# AZPR_EvBoard.net
KiCad netlist of a schematic drawn in EAGLE
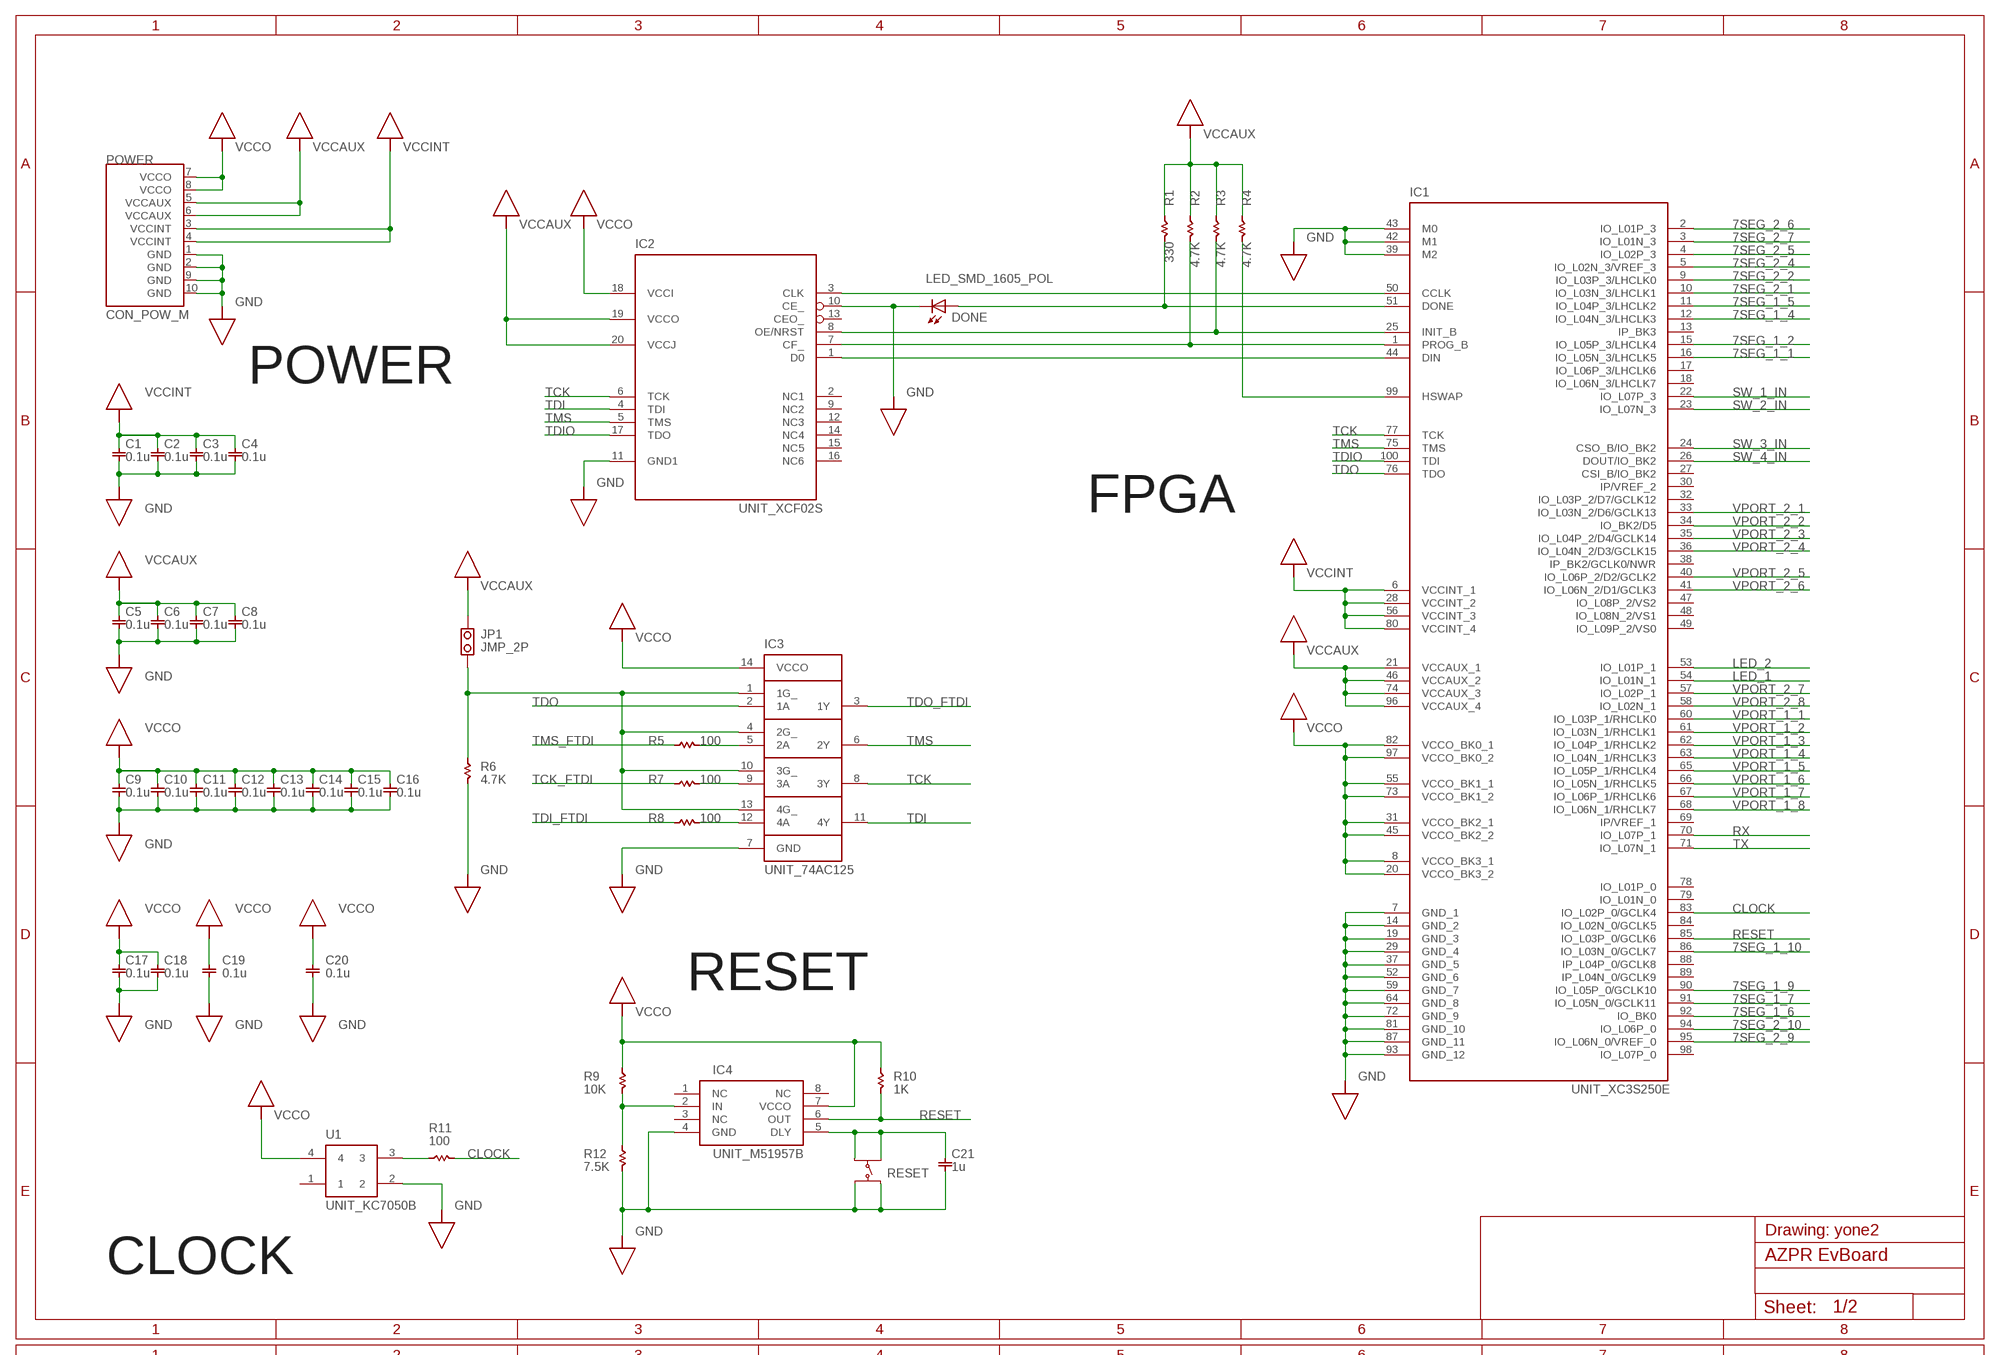
[diagram p0: schematic, sheet 1, part 1 of 2]
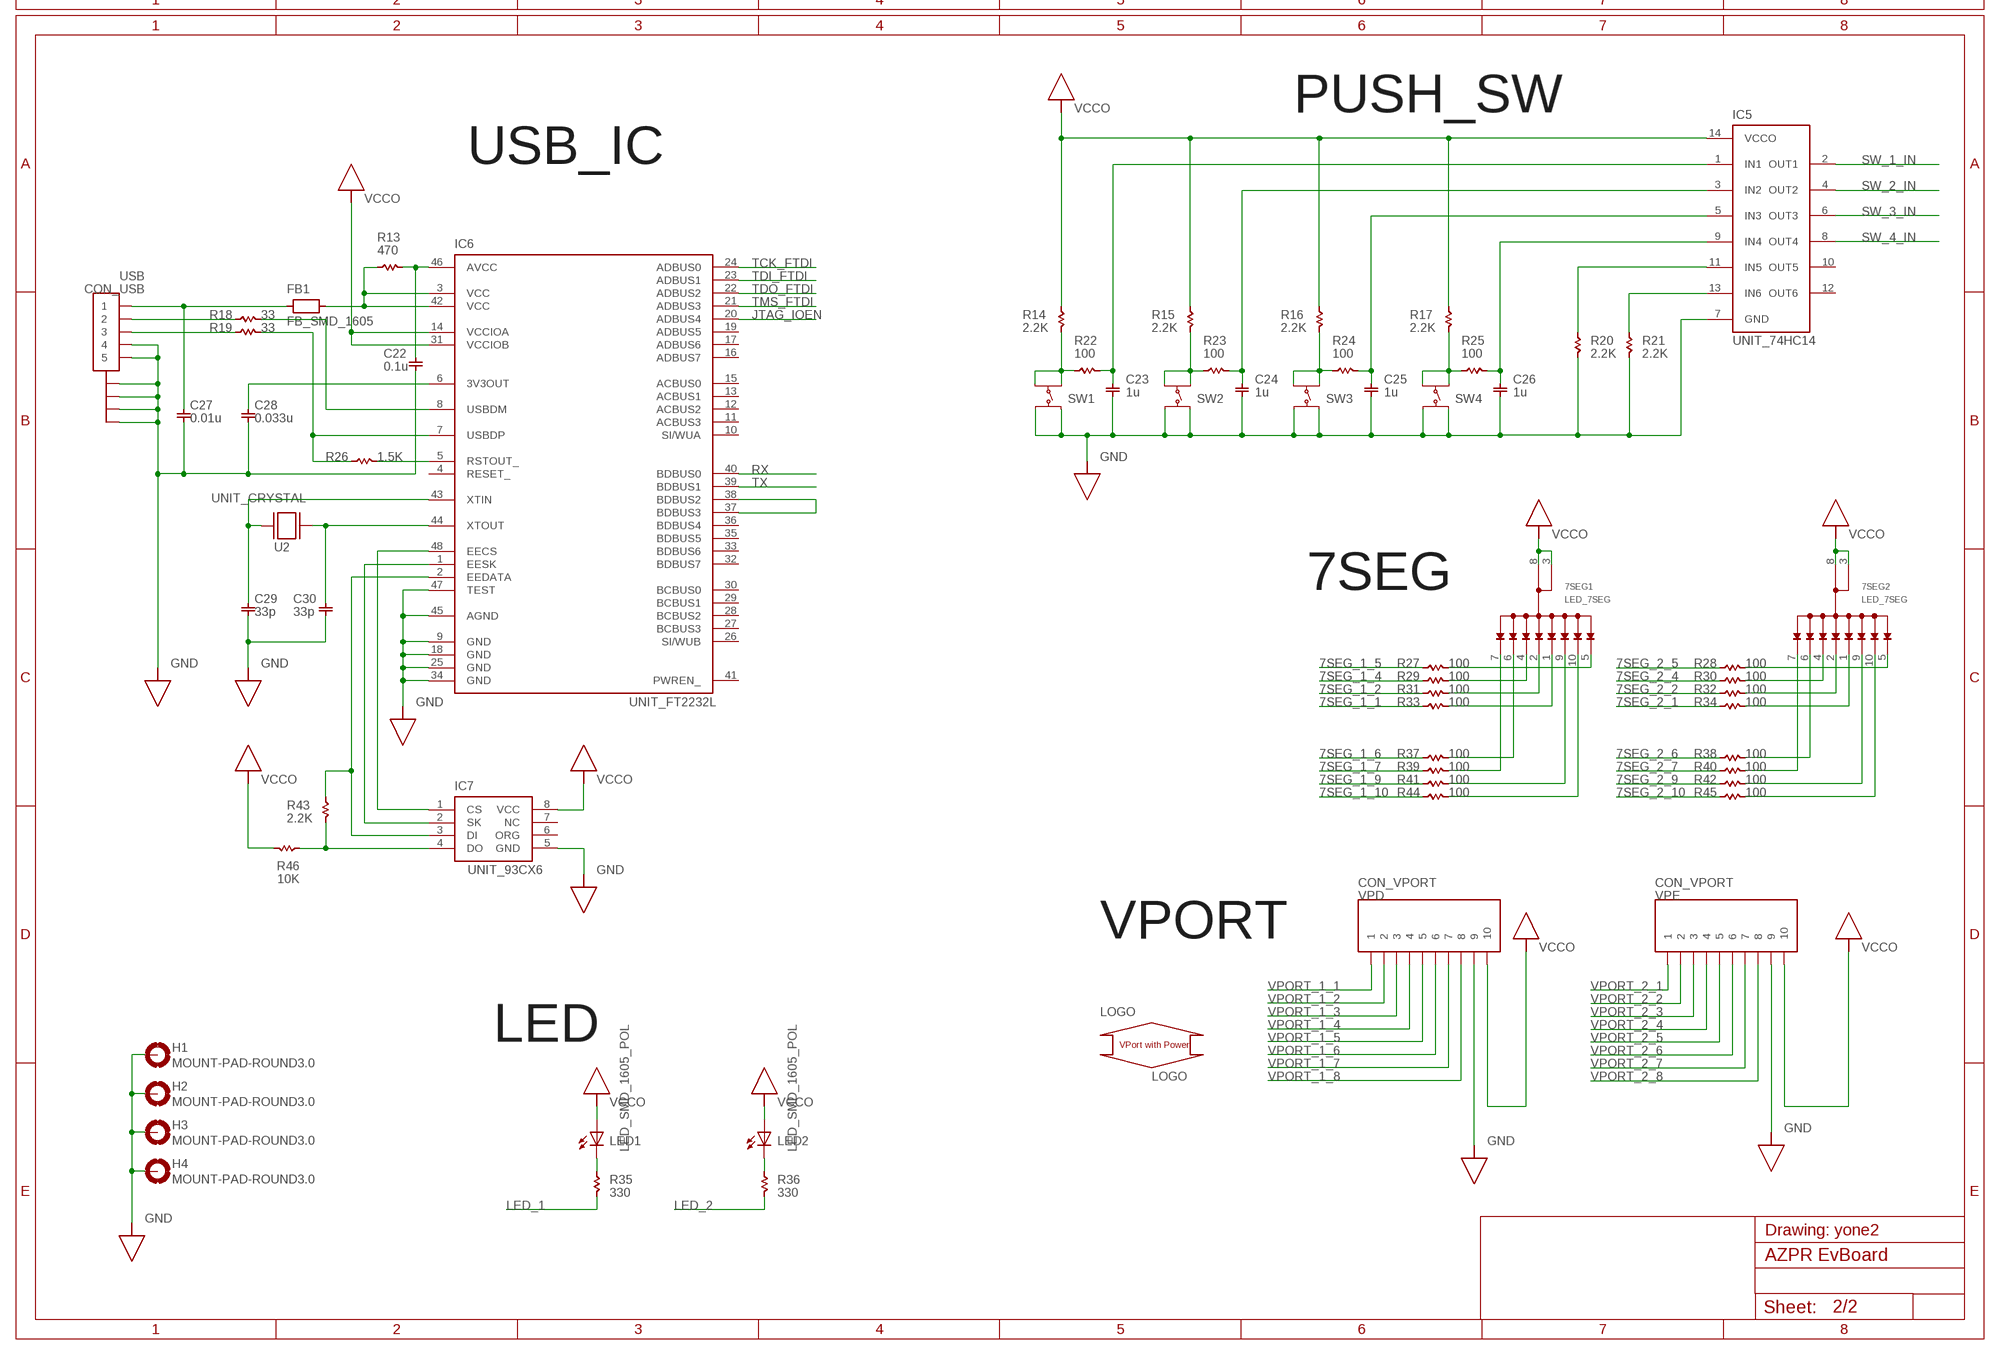
[diagram p1: schematic, sheet 1, part 2 of 2]

(export (version "E")
  (design (tool "Eeschema 10.0.6"))
  (components
    (comp (ref "7SEG1")
      (value "LED_7SEG")
      (footprint "eagle-import:SMD_LED_7SEG")
      (libsource (lib "eagle-import") (part "LED_7SEG"))
    )
    (comp (ref "7SEG2")
      (value "LED_7SEG")
      (footprint "eagle-import:SMD_LED_7SEG")
      (libsource (lib "eagle-import") (part "LED_7SEG"))
    )
    (comp (ref "C1")
      (value "0.1u")
      (footprint "eagle-import:SMDPAD_1605_04INCH")
      (libsource (lib "eagle-import") (part "CAP_SMDPAD_1605_04INCH"))
    )
    (comp (ref "C2")
      (value "0.1u")
      (footprint "eagle-import:SMDPAD_1605_04INCH")
      (libsource (lib "eagle-import") (part "CAP_SMDPAD_1605_04INCH"))
    )
    (comp (ref "C3")
      (value "0.1u")
      (footprint "eagle-import:SMDPAD_1605_04INCH")
      (libsource (lib "eagle-import") (part "CAP_SMDPAD_1605_04INCH"))
    )
    (comp (ref "C4")
      (value "0.1u")
      (footprint "eagle-import:SMDPAD_1605_04INCH")
      (libsource (lib "eagle-import") (part "CAP_SMDPAD_1605_04INCH"))
    )
    (comp (ref "C5")
      (value "0.1u")
      (footprint "eagle-import:SMDPAD_1605_03INCH")
      (libsource (lib "eagle-import") (part "CAP_SMDPAD_1605_03INCH"))
    )
    (comp (ref "C6")
      (value "0.1u")
      (footprint "eagle-import:SMDPAD_1605_03INCH")
      (libsource (lib "eagle-import") (part "CAP_SMDPAD_1605_03INCH"))
    )
    (comp (ref "C7")
      (value "0.1u")
      (footprint "eagle-import:SMDPAD_1605_03INCH")
      (libsource (lib "eagle-import") (part "CAP_SMDPAD_1605_03INCH"))
    )
    (comp (ref "C8")
      (value "0.1u")
      (footprint "eagle-import:SMDPAD_1605_03INCH")
      (libsource (lib "eagle-import") (part "CAP_SMDPAD_1605_03INCH"))
    )
    (comp (ref "C9")
      (value "0.1u")
      (footprint "eagle-import:SMDPAD_1605_02INCH")
      (libsource (lib "eagle-import") (part "CAP_SMDPAD_1605_02INCH"))
    )
    (comp (ref "C10")
      (value "0.1u")
      (footprint "eagle-import:SMDPAD_1605_02INCH")
      (libsource (lib "eagle-import") (part "CAP_SMDPAD_1605_02INCH"))
    )
    (comp (ref "C11")
      (value "0.1u")
      (footprint "eagle-import:SMDPAD_1605_02INCH")
      (libsource (lib "eagle-import") (part "CAP_SMDPAD_1605_02INCH"))
    )
    (comp (ref "C12")
      (value "0.1u")
      (footprint "eagle-import:SMDPAD_1605_02INCH")
      (libsource (lib "eagle-import") (part "CAP_SMDPAD_1605_02INCH"))
    )
    (comp (ref "C13")
      (value "0.1u")
      (footprint "eagle-import:SMDPAD_1605_02INCH")
      (libsource (lib "eagle-import") (part "CAP_SMDPAD_1605_02INCH"))
    )
    (comp (ref "C14")
      (value "0.1u")
      (footprint "eagle-import:SMDPAD_1605_02INCH")
      (libsource (lib "eagle-import") (part "CAP_SMDPAD_1605_02INCH"))
    )
    (comp (ref "C15")
      (value "0.1u")
      (footprint "eagle-import:SMDPAD_1605_02INCH")
      (libsource (lib "eagle-import") (part "CAP_SMDPAD_1605_02INCH"))
    )
    (comp (ref "C16")
      (value "0.1u")
      (footprint "eagle-import:SMDPAD_1605_02INCH")
      (libsource (lib "eagle-import") (part "CAP_SMDPAD_1605_02INCH"))
    )
    (comp (ref "C17")
      (value "0.1u")
      (footprint "eagle-import:SMDPAD_1605_02INCH")
      (libsource (lib "eagle-import") (part "CAP_SMDPAD_1605_02INCH"))
    )
    (comp (ref "C18")
      (value "0.1u")
      (footprint "eagle-import:SMD_1605")
      (libsource (lib "eagle-import") (part "CAP_SMD_1605"))
    )
    (comp (ref "C19")
      (value "0.1u")
      (footprint "eagle-import:SMD_1605")
      (libsource (lib "eagle-import") (part "CAP_SMD_1605"))
    )
    (comp (ref "C20")
      (value "0.1u")
      (footprint "eagle-import:SMD_1605")
      (libsource (lib "eagle-import") (part "CAP_SMD_1605"))
    )
    (comp (ref "C21")
      (value "1u")
      (footprint "eagle-import:SMD_1605")
      (libsource (lib "eagle-import") (part "CAP_SMD_1605"))
    )
    (comp (ref "C22")
      (value "0.1u")
      (footprint "eagle-import:SMD_1605")
      (libsource (lib "eagle-import") (part "CAP_SMD_1605"))
    )
    (comp (ref "C23")
      (value "1u")
      (footprint "eagle-import:SMD_1605")
      (libsource (lib "eagle-import") (part "CAP_SMD_1605"))
    )
    (comp (ref "C24")
      (value "1u")
      (footprint "eagle-import:SMD_1605")
      (libsource (lib "eagle-import") (part "CAP_SMD_1605"))
    )
    (comp (ref "C25")
      (value "1u")
      (footprint "eagle-import:SMD_1605")
      (libsource (lib "eagle-import") (part "CAP_SMD_1605"))
    )
    (comp (ref "C26")
      (value "1u")
      (footprint "eagle-import:SMD_1605")
      (libsource (lib "eagle-import") (part "CAP_SMD_1605"))
    )
    (comp (ref "C27")
      (value "0.01u")
      (footprint "eagle-import:SMD_1605")
      (libsource (lib "eagle-import") (part "CAP_SMD_1605"))
    )
    (comp (ref "C28")
      (value "0.033u")
      (footprint "eagle-import:SMD_1605")
      (libsource (lib "eagle-import") (part "CAP_SMD_1605"))
    )
    (comp (ref "C29")
      (value "33p")
      (footprint "eagle-import:SMD_1605")
      (libsource (lib "eagle-import") (part "CAP_SMD_1605"))
    )
    (comp (ref "C30")
      (value "33p")
      (footprint "eagle-import:SMD_1605")
      (libsource (lib "eagle-import") (part "CAP_SMD_1605"))
    )
    (comp (ref "DONE")
      (value "LED_SMD_1605_POL")
      (footprint "eagle-import:SMD_1605_POL")
      (libsource (lib "eagle-import") (part "LED_SMD_1605_POL"))
    )
    (comp (ref "FB1")
      (value "FB_SMD_1605")
      (footprint "eagle-import:SMD_1605")
      (libsource (lib "eagle-import") (part "FB_SMD_1605"))
    )
    (comp (ref "H1")
      (value "MOUNT-PAD-ROUND3.0")
      (footprint "eagle-import:HOLE_32")
      (libsource (lib "eagle-import") (part "HOLE_32"))
    )
    (comp (ref "H2")
      (value "MOUNT-PAD-ROUND3.0")
      (footprint "eagle-import:HOLE_32")
      (libsource (lib "eagle-import") (part "HOLE_32"))
    )
    (comp (ref "H3")
      (value "MOUNT-PAD-ROUND3.0")
      (footprint "eagle-import:HOLE_32")
      (libsource (lib "eagle-import") (part "HOLE_32"))
    )
    (comp (ref "H4")
      (value "MOUNT-PAD-ROUND3.0")
      (footprint "eagle-import:HOLE_32")
      (libsource (lib "eagle-import") (part "HOLE_32"))
    )
    (comp (ref "IC1")
      (value "UNIT_XC3S250E")
      (footprint "eagle-import:SMD_VQ100")
      (libsource (lib "eagle-import") (part "UNIT_XC3S250E"))
    )
    (comp (ref "IC2")
      (value "UNIT_XCF02S")
      (footprint "eagle-import:SMD_VO20C")
      (libsource (lib "eagle-import") (part "UNIT_XCF02S"))
    )
    (comp (ref "IC3")
      (value "UNIT_74AC125")
      (footprint "eagle-import:SMD_SOP14")
      (libsource (lib "eagle-import") (part "UNIT_74AC125"))
    )
    (comp (ref "IC4")
      (value "UNIT_M51957B")
      (footprint "eagle-import:SMD_SOP8")
      (libsource (lib "eagle-import") (part "UNIT_M51957B"))
    )
    (comp (ref "IC5")
      (value "UNIT_74HC14")
      (footprint "eagle-import:SMD_SOP14")
      (libsource (lib "eagle-import") (part "UNIT_74HC14"))
    )
    (comp (ref "IC6")
      (value "UNIT_FT2232L")
      (footprint "eagle-import:SMD_LQFP48")
      (libsource (lib "eagle-import") (part "UNIT_FT2232L"))
    )
    (comp (ref "IC7")
      (value "UNIT_93CX6")
      (footprint "eagle-import:SMD_SOP8")
      (libsource (lib "eagle-import") (part "UNIT_93CX6"))
    )
    (comp (ref "JP1")
      (value "JMP_2P")
      (footprint "eagle-import:PAD_JMP_2P")
      (libsource (lib "eagle-import") (part "JMP_2P"))
    )
    (comp (ref "LED1")
      (value "LED_SMD_1605_POL")
      (footprint "eagle-import:SMD_1605_POL")
      (libsource (lib "eagle-import") (part "LED_SMD_1605_POL"))
    )
    (comp (ref "LED2")
      (value "LED_SMD_1605_POL")
      (footprint "eagle-import:SMD_1605_POL")
      (libsource (lib "eagle-import") (part "LED_SMD_1605_POL"))
    )
    (comp (ref "LOGO")
      (value "LOGO")
      (footprint "eagle-import:LOGO")
      (libsource (lib "eagle-import") (part "LOGO"))
    )
    (comp (ref "POWER")
      (value "CON_POW_M")
      (footprint "eagle-import:PAD_POW_M")
      (libsource (lib "eagle-import") (part "CON_POW_M"))
    )
    (comp (ref "R1")
      (value "330")
      (footprint "eagle-import:SMD_1605_R")
      (libsource (lib "eagle-import") (part "REG_SMD_1605"))
    )
    (comp (ref "R2")
      (value "4.7K")
      (footprint "eagle-import:SMD_1605_R")
      (libsource (lib "eagle-import") (part "REG_SMD_1605"))
    )
    (comp (ref "R3")
      (value "4.7K")
      (footprint "eagle-import:SMD_1605_R")
      (libsource (lib "eagle-import") (part "REG_SMD_1605"))
    )
    (comp (ref "R4")
      (value "4.7K")
      (footprint "eagle-import:SMD_1605_R")
      (libsource (lib "eagle-import") (part "REG_SMD_1605"))
    )
    (comp (ref "R5")
      (value "100")
      (footprint "eagle-import:SMD_1605_R")
      (libsource (lib "eagle-import") (part "REG_SMD_1605"))
    )
    (comp (ref "R6")
      (value "4.7K")
      (footprint "eagle-import:SMD_1605_R")
      (libsource (lib "eagle-import") (part "REG_SMD_1605"))
    )
    (comp (ref "R7")
      (value "100")
      (footprint "eagle-import:SMD_1605_R")
      (libsource (lib "eagle-import") (part "REG_SMD_1605"))
    )
    (comp (ref "R8")
      (value "100")
      (footprint "eagle-import:SMD_1605_R")
      (libsource (lib "eagle-import") (part "REG_SMD_1605"))
    )
    (comp (ref "R9")
      (value "10K")
      (footprint "eagle-import:SMD_1605_R")
      (libsource (lib "eagle-import") (part "REG_SMD_1605"))
    )
    (comp (ref "R10")
      (value "1K")
      (footprint "eagle-import:SMD_1605_R")
      (libsource (lib "eagle-import") (part "REG_SMD_1605"))
    )
    (comp (ref "R11")
      (value "100")
      (footprint "eagle-import:SMD_1605_R")
      (libsource (lib "eagle-import") (part "REG_SMD_1605"))
    )
    (comp (ref "R12")
      (value "7.5K")
      (footprint "eagle-import:SMD_1605_R")
      (libsource (lib "eagle-import") (part "REG_SMD_1605"))
    )
    (comp (ref "R13")
      (value "470")
      (footprint "eagle-import:SMD_1605_R")
      (libsource (lib "eagle-import") (part "REG_SMD_1605"))
    )
    (comp (ref "R14")
      (value "2.2K")
      (footprint "eagle-import:SMD_1605_R")
      (libsource (lib "eagle-import") (part "REG_SMD_1605"))
    )
    (comp (ref "R15")
      (value "2.2K")
      (footprint "eagle-import:SMD_1605_R")
      (libsource (lib "eagle-import") (part "REG_SMD_1605"))
    )
    (comp (ref "R16")
      (value "2.2K")
      (footprint "eagle-import:SMD_1605_R")
      (libsource (lib "eagle-import") (part "REG_SMD_1605"))
    )
    (comp (ref "R17")
      (value "2.2K")
      (footprint "eagle-import:SMD_1605_R")
      (libsource (lib "eagle-import") (part "REG_SMD_1605"))
    )
    (comp (ref "R18")
      (value "33")
      (footprint "eagle-import:SMD_1605_R")
      (libsource (lib "eagle-import") (part "REG_SMD_1605"))
    )
    (comp (ref "R19")
      (value "33")
      (footprint "eagle-import:SMD_1605_R")
      (libsource (lib "eagle-import") (part "REG_SMD_1605"))
    )
    (comp (ref "R20")
      (value "2.2K")
      (footprint "eagle-import:SMD_1605_R")
      (libsource (lib "eagle-import") (part "REG_SMD_1605"))
    )
    (comp (ref "R21")
      (value "2.2K")
      (footprint "eagle-import:SMD_1605_R")
      (libsource (lib "eagle-import") (part "REG_SMD_1605"))
    )
    (comp (ref "R22")
      (value "100")
      (footprint "eagle-import:SMD_1605_R")
      (libsource (lib "eagle-import") (part "REG_SMD_1605"))
    )
    (comp (ref "R23")
      (value "100")
      (footprint "eagle-import:SMD_1605_R")
      (libsource (lib "eagle-import") (part "REG_SMD_1605"))
    )
    (comp (ref "R24")
      (value "100")
      (footprint "eagle-import:SMD_1605_R")
      (libsource (lib "eagle-import") (part "REG_SMD_1605"))
    )
    (comp (ref "R25")
      (value "100")
      (footprint "eagle-import:SMD_1605_R")
      (libsource (lib "eagle-import") (part "REG_SMD_1605"))
    )
    (comp (ref "R26")
      (value "1.5K")
      (footprint "eagle-import:SMD_1605_R")
      (libsource (lib "eagle-import") (part "REG_SMD_1605"))
    )
    (comp (ref "R27")
      (value "100")
      (footprint "eagle-import:SMD_1605_R")
      (libsource (lib "eagle-import") (part "REG_SMD_1605"))
    )
    (comp (ref "R28")
      (value "100")
      (footprint "eagle-import:SMD_1605_R")
      (libsource (lib "eagle-import") (part "REG_SMD_1605"))
    )
    (comp (ref "R29")
      (value "100")
      (footprint "eagle-import:SMD_1605_R")
      (libsource (lib "eagle-import") (part "REG_SMD_1605"))
    )
    (comp (ref "R30")
      (value "100")
      (footprint "eagle-import:SMD_1605_R")
      (libsource (lib "eagle-import") (part "REG_SMD_1605"))
    )
    (comp (ref "R31")
      (value "100")
      (footprint "eagle-import:SMD_1605_R")
      (libsource (lib "eagle-import") (part "REG_SMD_1605"))
    )
    (comp (ref "R32")
      (value "100")
      (footprint "eagle-import:SMD_1605_R")
      (libsource (lib "eagle-import") (part "REG_SMD_1605"))
    )
    (comp (ref "R33")
      (value "100")
      (footprint "eagle-import:SMD_1605_R")
      (libsource (lib "eagle-import") (part "REG_SMD_1605"))
    )
    (comp (ref "R34")
      (value "100")
      (footprint "eagle-import:SMD_1605_R")
      (libsource (lib "eagle-import") (part "REG_SMD_1605"))
    )
    (comp (ref "R35")
      (value "330")
      (footprint "eagle-import:SMD_1605_R")
      (libsource (lib "eagle-import") (part "REG_SMD_1605"))
    )
    (comp (ref "R36")
      (value "330")
      (footprint "eagle-import:SMD_1605_R")
      (libsource (lib "eagle-import") (part "REG_SMD_1605"))
    )
    (comp (ref "R37")
      (value "100")
      (footprint "eagle-import:SMD_1605_R")
      (libsource (lib "eagle-import") (part "REG_SMD_1605"))
    )
    (comp (ref "R38")
      (value "100")
      (footprint "eagle-import:SMD_1605_R")
      (libsource (lib "eagle-import") (part "REG_SMD_1605"))
    )
    (comp (ref "R39")
      (value "100")
      (footprint "eagle-import:SMD_1605_R")
      (libsource (lib "eagle-import") (part "REG_SMD_1605"))
    )
    (comp (ref "R40")
      (value "100")
      (footprint "eagle-import:SMD_1605_R")
      (libsource (lib "eagle-import") (part "REG_SMD_1605"))
    )
    (comp (ref "R41")
      (value "100")
      (footprint "eagle-import:SMD_1605_R")
      (libsource (lib "eagle-import") (part "REG_SMD_1605"))
    )
    (comp (ref "R42")
      (value "100")
      (footprint "eagle-import:SMD_1605_R")
      (libsource (lib "eagle-import") (part "REG_SMD_1605"))
    )
    (comp (ref "R43")
      (value "2.2K")
      (footprint "eagle-import:SMD_1605_R")
      (libsource (lib "eagle-import") (part "REG_SMD_1605"))
    )
    (comp (ref "R44")
      (value "100")
      (footprint "eagle-import:SMD_1605_R")
      (libsource (lib "eagle-import") (part "REG_SMD_1605"))
    )
    (comp (ref "R45")
      (value "100")
      (footprint "eagle-import:SMD_1605_R")
      (libsource (lib "eagle-import") (part "REG_SMD_1605"))
    )
    (comp (ref "R46")
      (value "10K")
      (footprint "eagle-import:SMD_1605_R")
      (libsource (lib "eagle-import") (part "REG_SMD_1605"))
    )
    (comp (ref "RESET")
      (value "SW_PUSH")
      (footprint "eagle-import:SMD_SW_PUSH")
      (libsource (lib "eagle-import") (part "SW_PUSH"))
    )
    (comp (ref "SW1")
      (value "SW_PUSH")
      (footprint "eagle-import:SMD_SW_PUSH")
      (libsource (lib "eagle-import") (part "SW_PUSH"))
    )
    (comp (ref "SW2")
      (value "SW_PUSH")
      (footprint "eagle-import:SMD_SW_PUSH")
      (libsource (lib "eagle-import") (part "SW_PUSH"))
    )
    (comp (ref "SW3")
      (value "SW_PUSH")
      (footprint "eagle-import:SMD_SW_PUSH")
      (libsource (lib "eagle-import") (part "SW_PUSH"))
    )
    (comp (ref "SW4")
      (value "SW_PUSH")
      (footprint "eagle-import:SMD_SW_PUSH")
      (libsource (lib "eagle-import") (part "SW_PUSH"))
    )
    (comp (ref "U1")
      (value "UNIT_KC7050B")
      (footprint "eagle-import:SMD_KC7050B")
      (libsource (lib "eagle-import") (part "UNIT_KC7050B"))
    )
    (comp (ref "U2")
      (value "UNIT_CRYSTAL")
      (footprint "eagle-import:SMD_HC-49_S")
      (libsource (lib "eagle-import") (part "UNIT_CRYSTAL"))
    )
    (comp (ref "USB")
      (value "CON_USB")
      (footprint "eagle-import:SMD_USB")
      (libsource (lib "eagle-import") (part "CON_USB"))
    )
    (comp (ref "VPD")
      (value "CON_VPORT")
      (footprint "eagle-import:PAD_VPORT")
      (libsource (lib "eagle-import") (part "CON_VPORT"))
    )
    (comp (ref "VPE")
      (value "CON_VPORT")
      (footprint "eagle-import:PAD_VPORT")
      (libsource (lib "eagle-import") (part "CON_VPORT"))
    )
  )
  (nets
    (net (code "1") (name "/7SEG_1_1") (class "Default")
      (node (ref "IC1") (pin "16") (pinfunction "IO_L05N_3/LHCLK5_16") (pintype "bidirectional"))
      (node (ref "R33") (pin "1") (pinfunction "1_1") (pintype "bidirectional"))
    )
    (net (code "2") (name "/7SEG_1_2") (class "Default")
      (node (ref "IC1") (pin "15") (pinfunction "IO_L05P_3/LHCLK4_15") (pintype "bidirectional"))
      (node (ref "R31") (pin "1") (pinfunction "1_1") (pintype "bidirectional"))
    )
    (net (code "3") (name "/7SEG_1_4") (class "Default")
      (node (ref "IC1") (pin "12") (pinfunction "IO_L04N_3/LHCLK3_12") (pintype "bidirectional"))
      (node (ref "R29") (pin "1") (pinfunction "1_1") (pintype "bidirectional"))
    )
    (net (code "4") (name "/7SEG_1_5") (class "Default")
      (node (ref "IC1") (pin "11") (pinfunction "IO_L04P_3/LHCLK2_11") (pintype "bidirectional"))
      (node (ref "R27") (pin "1") (pinfunction "1_1") (pintype "bidirectional"))
    )
    (net (code "5") (name "/7SEG_1_6") (class "Default")
      (node (ref "IC1") (pin "92") (pinfunction "IO_BK0_92") (pintype "bidirectional"))
      (node (ref "R37") (pin "1") (pinfunction "1_1") (pintype "bidirectional"))
    )
    (net (code "6") (name "/7SEG_1_7") (class "Default")
      (node (ref "IC1") (pin "91") (pinfunction "IO_L05N_0/GCLK11_91") (pintype "bidirectional"))
      (node (ref "R39") (pin "1") (pinfunction "1_1") (pintype "bidirectional"))
    )
    (net (code "7") (name "/7SEG_1_9") (class "Default")
      (node (ref "IC1") (pin "90") (pinfunction "IO_L05P_0/GCLK10_90") (pintype "bidirectional"))
      (node (ref "R41") (pin "1") (pinfunction "1_1") (pintype "bidirectional"))
    )
    (net (code "8") (name "/7SEG_1_10") (class "Default")
      (node (ref "IC1") (pin "86") (pinfunction "IO_L03N_0/GCLK7_86") (pintype "bidirectional"))
      (node (ref "R44") (pin "1") (pinfunction "1_1") (pintype "bidirectional"))
    )
    (net (code "9") (name "/7SEG_2_1") (class "Default")
      (node (ref "IC1") (pin "10") (pinfunction "IO_L03N_3/LHCLK1_10") (pintype "bidirectional"))
      (node (ref "R34") (pin "1") (pinfunction "1_1") (pintype "bidirectional"))
    )
    (net (code "10") (name "/7SEG_2_2") (class "Default")
      (node (ref "IC1") (pin "9") (pinfunction "IO_L03P_3/LHCLK0_9") (pintype "bidirectional"))
      (node (ref "R32") (pin "1") (pinfunction "1_1") (pintype "bidirectional"))
    )
    (net (code "11") (name "/7SEG_2_4") (class "Default")
      (node (ref "IC1") (pin "5") (pinfunction "IO_L02N_3/VREF_3_5") (pintype "bidirectional"))
      (node (ref "R30") (pin "1") (pinfunction "1_1") (pintype "bidirectional"))
    )
    (net (code "12") (name "/7SEG_2_5") (class "Default")
      (node (ref "IC1") (pin "4") (pinfunction "IO_L02P_3_4") (pintype "bidirectional"))
      (node (ref "R28") (pin "1") (pinfunction "1_1") (pintype "bidirectional"))
    )
    (net (code "13") (name "/7SEG_2_6") (class "Default")
      (node (ref "IC1") (pin "2") (pinfunction "IO_L01P_3_2") (pintype "bidirectional"))
      (node (ref "R38") (pin "1") (pinfunction "1_1") (pintype "bidirectional"))
    )
    (net (code "14") (name "/7SEG_2_7") (class "Default")
      (node (ref "IC1") (pin "3") (pinfunction "IO_L01N_3_3") (pintype "bidirectional"))
      (node (ref "R40") (pin "1") (pinfunction "1_1") (pintype "bidirectional"))
    )
    (net (code "15") (name "/7SEG_2_9") (class "Default")
      (node (ref "IC1") (pin "95") (pinfunction "IO_L06N_0/VREF_0_95") (pintype "bidirectional"))
      (node (ref "R42") (pin "1") (pinfunction "1_1") (pintype "bidirectional"))
    )
    (net (code "16") (name "/7SEG_2_10") (class "Default")
      (node (ref "IC1") (pin "94") (pinfunction "IO_L06P_0_94") (pintype "bidirectional"))
      (node (ref "R45") (pin "1") (pinfunction "1_1") (pintype "bidirectional"))
    )
    (net (code "17") (name "/CLOCK") (class "Default")
      (node (ref "IC1") (pin "83") (pinfunction "IO_L02P_0/GCLK4_83") (pintype "bidirectional"))
      (node (ref "R11") (pin "2") (pinfunction "2_2") (pintype "bidirectional"))
    )
    (net (code "18") (name "/JTAG_IOEN") (class "Default")
      (node (ref "IC6") (pin "20") (pinfunction "ADBUS4_20") (pintype "bidirectional"))
    )
    (net (code "19") (name "/LED_1") (class "Default")
      (node (ref "IC1") (pin "54") (pinfunction "IO_L01N_1_54") (pintype "bidirectional"))
      (node (ref "R35") (pin "2") (pinfunction "2_2") (pintype "bidirectional"))
    )
    (net (code "20") (name "/LED_2") (class "Default")
      (node (ref "IC1") (pin "53") (pinfunction "IO_L01P_1_53") (pintype "bidirectional"))
      (node (ref "R36") (pin "2") (pinfunction "2_2") (pintype "bidirectional"))
    )
    (net (code "21") (name "/RESET") (class "Default")
      (node (ref "IC1") (pin "85") (pinfunction "IO_L03P_0/GCLK6_85") (pintype "bidirectional"))
      (node (ref "IC4") (pin "6") (pinfunction "OUT_6") (pintype "bidirectional"))
      (node (ref "R10") (pin "2") (pinfunction "2_2") (pintype "bidirectional"))
    )
    (net (code "22") (name "/RX") (class "Default")
      (node (ref "IC1") (pin "70") (pinfunction "IO_L07P_1_70") (pintype "bidirectional"))
      (node (ref "IC6") (pin "40") (pinfunction "BDBUS0_40") (pintype "bidirectional"))
    )
    (net (code "23") (name "/SW_1_IN") (class "Default")
      (node (ref "IC1") (pin "22") (pinfunction "IO_L07P_3_22") (pintype "bidirectional"))
      (node (ref "IC5") (pin "2") (pinfunction "OUT1_2") (pintype "bidirectional"))
    )
    (net (code "24") (name "/SW_2_IN") (class "Default")
      (node (ref "IC1") (pin "23") (pinfunction "IO_L07N_3_23") (pintype "bidirectional"))
      (node (ref "IC5") (pin "4") (pinfunction "OUT2_4") (pintype "bidirectional"))
    )
    (net (code "25") (name "/SW_3_IN") (class "Default")
      (node (ref "IC1") (pin "24") (pinfunction "CSO_B/IO_BK2_24") (pintype "bidirectional"))
      (node (ref "IC5") (pin "6") (pinfunction "OUT3_6") (pintype "bidirectional"))
    )
    (net (code "26") (name "/SW_4_IN") (class "Default")
      (node (ref "IC1") (pin "26") (pinfunction "DOUT/IO_BK2_26") (pintype "bidirectional"))
      (node (ref "IC5") (pin "8") (pinfunction "OUT4_8") (pintype "bidirectional"))
    )
    (net (code "27") (name "/TCK") (class "Default")
      (node (ref "IC1") (pin "77") (pinfunction "TCK_77") (pintype "bidirectional"))
      (node (ref "IC2") (pin "6") (pinfunction "TCK_6") (pintype "bidirectional"))
      (node (ref "IC3") (pin "8") (pinfunction "3Y_8") (pintype "bidirectional"))
    )
    (net (code "28") (name "/TCK_FTDI") (class "Default")
      (node (ref "IC6") (pin "24") (pinfunction "ADBUS0_24") (pintype "bidirectional"))
      (node (ref "R7") (pin "1") (pinfunction "1_1") (pintype "bidirectional"))
    )
    (net (code "29") (name "/TDI") (class "Default")
      (node (ref "IC2") (pin "4") (pinfunction "TDI_4") (pintype "bidirectional"))
      (node (ref "IC3") (pin "11") (pinfunction "4Y_11") (pintype "bidirectional"))
    )
    (net (code "30") (name "/TDIO") (class "Default")
      (node (ref "IC1") (pin "100") (pinfunction "TDI_100") (pintype "bidirectional"))
      (node (ref "IC2") (pin "17") (pinfunction "TDO_17") (pintype "bidirectional"))
    )
    (net (code "31") (name "/TDI_FTDI") (class "Default")
      (node (ref "IC6") (pin "23") (pinfunction "ADBUS1_23") (pintype "bidirectional"))
      (node (ref "R8") (pin "1") (pinfunction "1_1") (pintype "bidirectional"))
    )
    (net (code "32") (name "/TDO") (class "Default")
      (node (ref "IC1") (pin "76") (pinfunction "TDO_76") (pintype "bidirectional"))
      (node (ref "IC3") (pin "2") (pinfunction "1A_2") (pintype "bidirectional"))
    )
    (net (code "33") (name "/TDO_FTDI") (class "Default")
      (node (ref "IC3") (pin "3") (pinfunction "1Y_3") (pintype "bidirectional"))
      (node (ref "IC6") (pin "22") (pinfunction "ADBUS2_22") (pintype "bidirectional"))
    )
    (net (code "34") (name "/TMS") (class "Default")
      (node (ref "IC1") (pin "75") (pinfunction "TMS_75") (pintype "bidirectional"))
      (node (ref "IC2") (pin "5") (pinfunction "TMS_5") (pintype "bidirectional"))
      (node (ref "IC3") (pin "6") (pinfunction "2Y_6") (pintype "bidirectional"))
    )
    (net (code "35") (name "/TMS_FTDI") (class "Default")
      (node (ref "IC6") (pin "21") (pinfunction "ADBUS3_21") (pintype "bidirectional"))
      (node (ref "R5") (pin "1") (pinfunction "1_1") (pintype "bidirectional"))
    )
    (net (code "36") (name "/TX") (class "Default")
      (node (ref "IC1") (pin "71") (pinfunction "IO_L07N_1_71") (pintype "bidirectional"))
      (node (ref "IC6") (pin "39") (pinfunction "BDBUS1_39") (pintype "bidirectional"))
    )
    (net (code "37") (name "/VPORT_1_1") (class "Default")
      (node (ref "IC1") (pin "60") (pinfunction "IO_L03P_1/RHCLK0_60") (pintype "bidirectional"))
      (node (ref "VPD") (pin "1") (pinfunction "1_1") (pintype "power_in"))
    )
    (net (code "38") (name "/VPORT_1_2") (class "Default")
      (node (ref "IC1") (pin "61") (pinfunction "IO_L03N_1/RHCLK1_61") (pintype "bidirectional"))
      (node (ref "VPD") (pin "2") (pinfunction "2_2") (pintype "power_in"))
    )
    (net (code "39") (name "/VPORT_1_3") (class "Default")
      (node (ref "IC1") (pin "62") (pinfunction "IO_L04P_1/RHCLK2_62") (pintype "bidirectional"))
      (node (ref "VPD") (pin "3") (pinfunction "3_3") (pintype "power_in"))
    )
    (net (code "40") (name "/VPORT_1_4") (class "Default")
      (node (ref "IC1") (pin "63") (pinfunction "IO_L04N_1/RHCLK3_63") (pintype "bidirectional"))
      (node (ref "VPD") (pin "4") (pinfunction "4_4") (pintype "power_in"))
    )
    (net (code "41") (name "/VPORT_1_5") (class "Default")
      (node (ref "IC1") (pin "65") (pinfunction "IO_L05P_1/RHCLK4_65") (pintype "bidirectional"))
      (node (ref "VPD") (pin "5") (pinfunction "5_5") (pintype "power_in"))
    )
    (net (code "42") (name "/VPORT_1_6") (class "Default")
      (node (ref "IC1") (pin "66") (pinfunction "IO_L05N_1/RHCLK5_66") (pintype "bidirectional"))
      (node (ref "VPD") (pin "6") (pinfunction "6_6") (pintype "power_in"))
    )
    (net (code "43") (name "/VPORT_1_7") (class "Default")
      (node (ref "IC1") (pin "67") (pinfunction "IO_L06P_1/RHCLK6_67") (pintype "bidirectional"))
      (node (ref "VPD") (pin "7") (pinfunction "7_7") (pintype "power_in"))
    )
    (net (code "44") (name "/VPORT_1_8") (class "Default")
      (node (ref "IC1") (pin "68") (pinfunction "IO_L06N_1/RHCLK7_68") (pintype "bidirectional"))
      (node (ref "VPD") (pin "8") (pinfunction "8_8") (pintype "power_in"))
    )
    (net (code "45") (name "/VPORT_2_1") (class "Default")
      (node (ref "IC1") (pin "33") (pinfunction "IO_L03N_2/D6/GCLK13_33") (pintype "bidirectional"))
      (node (ref "VPE") (pin "1") (pinfunction "1_1") (pintype "power_in"))
    )
    (net (code "46") (name "/VPORT_2_2") (class "Default")
      (node (ref "IC1") (pin "34") (pinfunction "IO_BK2/D5_34") (pintype "bidirectional"))
      (node (ref "VPE") (pin "2") (pinfunction "2_2") (pintype "power_in"))
    )
    (net (code "47") (name "/VPORT_2_3") (class "Default")
      (node (ref "IC1") (pin "35") (pinfunction "IO_L04P_2/D4/GCLK14_35") (pintype "bidirectional"))
      (node (ref "VPE") (pin "3") (pinfunction "3_3") (pintype "power_in"))
    )
    (net (code "48") (name "/VPORT_2_4") (class "Default")
      (node (ref "IC1") (pin "36") (pinfunction "IO_L04N_2/D3/GCLK15_36") (pintype "bidirectional"))
      (node (ref "VPE") (pin "4") (pinfunction "4_4") (pintype "power_in"))
    )
    (net (code "49") (name "/VPORT_2_5") (class "Default")
      (node (ref "IC1") (pin "40") (pinfunction "IO_L06P_2/D2/GCLK2_40") (pintype "bidirectional"))
      (node (ref "VPE") (pin "5") (pinfunction "5_5") (pintype "power_in"))
    )
    (net (code "50") (name "/VPORT_2_6") (class "Default")
      (node (ref "IC1") (pin "41") (pinfunction "IO_L06N_2/D1/GCLK3_41") (pintype "bidirectional"))
      (node (ref "VPE") (pin "6") (pinfunction "6_6") (pintype "power_in"))
    )
    (net (code "51") (name "/VPORT_2_7") (class "Default")
      (node (ref "IC1") (pin "57") (pinfunction "IO_L02P_1_57") (pintype "bidirectional"))
      (node (ref "VPE") (pin "7") (pinfunction "7_7") (pintype "power_in"))
    )
    (net (code "52") (name "/VPORT_2_8") (class "Default")
      (node (ref "IC1") (pin "58") (pinfunction "IO_L02N_1_58") (pintype "bidirectional"))
      (node (ref "VPE") (pin "8") (pinfunction "8_8") (pintype "power_in"))
    )
    (net (code "53") (name "GND") (class "Default")
      (node (ref "C1") (pin "P$2") (pinfunction "2_P$2") (pintype "bidirectional"))
      (node (ref "C10") (pin "P$2") (pinfunction "2_P$2") (pintype "bidirectional"))
      (node (ref "C11") (pin "P$2") (pinfunction "2_P$2") (pintype "bidirectional"))
      (node (ref "C12") (pin "P$2") (pinfunction "2_P$2") (pintype "bidirectional"))
      (node (ref "C13") (pin "P$2") (pinfunction "2_P$2") (pintype "bidirectional"))
      (node (ref "C14") (pin "P$2") (pinfunction "2_P$2") (pintype "bidirectional"))
      (node (ref "C15") (pin "P$2") (pinfunction "2_P$2") (pintype "bidirectional"))
      (node (ref "C16") (pin "P$2") (pinfunction "2_P$2") (pintype "bidirectional"))
      (node (ref "C17") (pin "P$2") (pinfunction "2_P$2") (pintype "bidirectional"))
      (node (ref "C18") (pin "2") (pinfunction "2_2") (pintype "bidirectional"))
      (node (ref "C19") (pin "2") (pinfunction "2_2") (pintype "bidirectional"))
      (node (ref "C2") (pin "P$2") (pinfunction "2_P$2") (pintype "bidirectional"))
      (node (ref "C20") (pin "2") (pinfunction "2_2") (pintype "bidirectional"))
      (node (ref "C21") (pin "2") (pinfunction "2_2") (pintype "bidirectional"))
      (node (ref "C22") (pin "2") (pinfunction "2_2") (pintype "bidirectional"))
      (node (ref "C23") (pin "2") (pinfunction "2_2") (pintype "bidirectional"))
      (node (ref "C24") (pin "2") (pinfunction "2_2") (pintype "bidirectional"))
      (node (ref "C25") (pin "2") (pinfunction "2_2") (pintype "bidirectional"))
      (node (ref "C26") (pin "2") (pinfunction "2_2") (pintype "bidirectional"))
      (node (ref "C27") (pin "2") (pinfunction "2_2") (pintype "bidirectional"))
      (node (ref "C28") (pin "2") (pinfunction "2_2") (pintype "bidirectional"))
      (node (ref "C29") (pin "2") (pinfunction "2_2") (pintype "bidirectional"))
      (node (ref "C3") (pin "P$2") (pinfunction "2_P$2") (pintype "bidirectional"))
      (node (ref "C30") (pin "2") (pinfunction "2_2") (pintype "bidirectional"))
      (node (ref "C4") (pin "P$2") (pinfunction "2_P$2") (pintype "bidirectional"))
      (node (ref "C5") (pin "P$2") (pinfunction "2_P$2") (pintype "bidirectional"))
      (node (ref "C6") (pin "P$2") (pinfunction "2_P$2") (pintype "bidirectional"))
      (node (ref "C7") (pin "P$2") (pinfunction "2_P$2") (pintype "bidirectional"))
      (node (ref "C8") (pin "P$2") (pinfunction "2_P$2") (pintype "bidirectional"))
      (node (ref "C9") (pin "P$2") (pinfunction "2_P$2") (pintype "bidirectional"))
      (node (ref "DONE") (pin "C") (pinfunction "C_C") (pintype "passive"))
      (node (ref "H1") (pin "B3,2") (pinfunction "MOUNT_B3,2") (pintype "passive"))
      (node (ref "H2") (pin "B3,2") (pinfunction "MOUNT_B3,2") (pintype "passive"))
      (node (ref "H3") (pin "B3,2") (pinfunction "MOUNT_B3,2") (pintype "passive"))
      (node (ref "H4") (pin "B3,2") (pinfunction "MOUNT_B3,2") (pintype "passive"))
      (node (ref "IC1") (pin "14") (pinfunction "GND_2_14") (pintype "power_in"))
      (node (ref "IC1") (pin "19") (pinfunction "GND_3_19") (pintype "power_in"))
      (node (ref "IC1") (pin "29") (pinfunction "GND_4_29") (pintype "power_in"))
      (node (ref "IC1") (pin "37") (pinfunction "GND_5_37") (pintype "power_in"))
      (node (ref "IC1") (pin "39") (pinfunction "M2_39") (pintype "bidirectional"))
      (node (ref "IC1") (pin "42") (pinfunction "M1_42") (pintype "bidirectional"))
      (node (ref "IC1") (pin "43") (pinfunction "M0_43") (pintype "bidirectional"))
      (node (ref "IC1") (pin "52") (pinfunction "GND_6_52") (pintype "power_in"))
      (node (ref "IC1") (pin "59") (pinfunction "GND_7_59") (pintype "power_in"))
      (node (ref "IC1") (pin "64") (pinfunction "GND_8_64") (pintype "power_in"))
      (node (ref "IC1") (pin "7") (pinfunction "GND_1_7") (pintype "power_in"))
      (node (ref "IC1") (pin "72") (pinfunction "GND_9_72") (pintype "power_in"))
      (node (ref "IC1") (pin "81") (pinfunction "GND_10_81") (pintype "power_in"))
      (node (ref "IC1") (pin "87") (pinfunction "GND_11_87") (pintype "power_in"))
      (node (ref "IC1") (pin "93") (pinfunction "GND_12_93") (pintype "power_in"))
      (node (ref "IC2") (pin "10") (pinfunction "CE__10") (pintype "bidirectional"))
      (node (ref "IC2") (pin "11") (pinfunction "GND1_11") (pintype "power_in"))
      (node (ref "IC3") (pin "7") (pinfunction "GND_7") (pintype "bidirectional"))
      (node (ref "IC4") (pin "4") (pinfunction "GND_4") (pintype "power_in"))
      (node (ref "IC5") (pin "7") (pinfunction "GND_7") (pintype "power_in"))
      (node (ref "IC6") (pin "18") (pinfunction "GND_18") (pintype "power_in"))
      (node (ref "IC6") (pin "25") (pinfunction "GND_25") (pintype "power_in"))
      (node (ref "IC6") (pin "34") (pinfunction "GND_34") (pintype "power_in"))
      (node (ref "IC6") (pin "45") (pinfunction "AGND_45") (pintype "power_in"))
      (node (ref "IC6") (pin "47") (pinfunction "TEST_47") (pintype "bidirectional"))
      (node (ref "IC6") (pin "9") (pinfunction "GND_9") (pintype "power_in"))
      (node (ref "IC7") (pin "5") (pinfunction "GND_5") (pintype "bidirectional"))
      (node (ref "POWER") (pin "1") (pinfunction "GND_1") (pintype "power_in"))
      (node (ref "POWER") (pin "10") (pinfunction "GND_10") (pintype "power_in"))
      (node (ref "POWER") (pin "2") (pinfunction "GND_2") (pintype "power_in"))
      (node (ref "POWER") (pin "9") (pinfunction "GND_9") (pintype "power_in"))
      (node (ref "R12") (pin "2") (pinfunction "2_2") (pintype "bidirectional"))
      (node (ref "R20") (pin "2") (pinfunction "2_2") (pintype "bidirectional"))
      (node (ref "R21") (pin "2") (pinfunction "2_2") (pintype "bidirectional"))
      (node (ref "R6") (pin "2") (pinfunction "2_2") (pintype "bidirectional"))
      (node (ref "RESET") (pin "3") (pinfunction "3_3") (pintype "bidirectional"))
      (node (ref "RESET") (pin "4") (pinfunction "4_4") (pintype "bidirectional"))
      (node (ref "SW1") (pin "3") (pinfunction "3_3") (pintype "bidirectional"))
      (node (ref "SW1") (pin "4") (pinfunction "4_4") (pintype "bidirectional"))
      (node (ref "SW2") (pin "3") (pinfunction "3_3") (pintype "bidirectional"))
      (node (ref "SW2") (pin "4") (pinfunction "4_4") (pintype "bidirectional"))
      (node (ref "SW3") (pin "3") (pinfunction "3_3") (pintype "bidirectional"))
      (node (ref "SW3") (pin "4") (pinfunction "4_4") (pintype "bidirectional"))
      (node (ref "SW4") (pin "3") (pinfunction "3_3") (pintype "bidirectional"))
      (node (ref "SW4") (pin "4") (pinfunction "4_4") (pintype "bidirectional"))
      (node (ref "U1") (pin "2") (pinfunction "2_2") (pintype "power_in"))
      (node (ref "USB") (pin "4") (pinfunction "4_4") (pintype "bidirectional"))
      (node (ref "USB") (pin "5") (pinfunction "5_5") (pintype "bidirectional"))
      (node (ref "USB") (pin "PAD@1") (pinfunction "PAD1_PAD@1") (pintype "power_in"))
      (node (ref "USB") (pin "PAD@2") (pinfunction "PAD2_PAD@2") (pintype "power_in"))
      (node (ref "USB") (pin "PAD@3") (pinfunction "PAD3_PAD@3") (pintype "power_in"))
      (node (ref "USB") (pin "PAD@4") (pinfunction "PAD4_PAD@4") (pintype "power_in"))
      (node (ref "VPD") (pin "9") (pinfunction "9_9") (pintype "power_in"))
      (node (ref "VPE") (pin "9") (pinfunction "9_9") (pintype "power_in"))
    )
    (net (code "54") (name "Net-(7SEG1-A)") (class "Default")
      (node (ref "7SEG1") (pin "7") (pinfunction "A_7") (pintype "bidirectional"))
      (node (ref "R39") (pin "2") (pinfunction "2_2") (pintype "bidirectional"))
    )
    (net (code "55") (name "Net-(7SEG1-B)") (class "Default")
      (node (ref "7SEG1") (pin "6") (pinfunction "B_6") (pintype "bidirectional"))
      (node (ref "R37") (pin "2") (pinfunction "2_2") (pintype "bidirectional"))
    )
    (net (code "56") (name "Net-(7SEG1-C)") (class "Default")
      (node (ref "7SEG1") (pin "4") (pinfunction "C_4") (pintype "bidirectional"))
      (node (ref "R29") (pin "2") (pinfunction "2_2") (pintype "bidirectional"))
    )
    (net (code "57") (name "Net-(7SEG1-D)") (class "Default")
      (node (ref "7SEG1") (pin "2") (pinfunction "D_2") (pintype "bidirectional"))
      (node (ref "R31") (pin "2") (pinfunction "2_2") (pintype "bidirectional"))
    )
    (net (code "58") (name "Net-(7SEG1-D.P)") (class "Default")
      (node (ref "7SEG1") (pin "5") (pinfunction "D.P_5") (pintype "bidirectional"))
      (node (ref "R27") (pin "2") (pinfunction "2_2") (pintype "bidirectional"))
    )
    (net (code "59") (name "Net-(7SEG1-E)") (class "Default")
      (node (ref "7SEG1") (pin "1") (pinfunction "E_1") (pintype "bidirectional"))
      (node (ref "R33") (pin "2") (pinfunction "2_2") (pintype "bidirectional"))
    )
    (net (code "60") (name "Net-(7SEG1-F)") (class "Default")
      (node (ref "7SEG1") (pin "9") (pinfunction "F_9") (pintype "bidirectional"))
      (node (ref "R41") (pin "2") (pinfunction "2_2") (pintype "bidirectional"))
    )
    (net (code "61") (name "Net-(7SEG1-G)") (class "Default")
      (node (ref "7SEG1") (pin "10") (pinfunction "G_10") (pintype "bidirectional"))
      (node (ref "R44") (pin "2") (pinfunction "2_2") (pintype "bidirectional"))
    )
    (net (code "62") (name "Net-(7SEG2-A)") (class "Default")
      (node (ref "7SEG2") (pin "7") (pinfunction "A_7") (pintype "bidirectional"))
      (node (ref "R40") (pin "2") (pinfunction "2_2") (pintype "bidirectional"))
    )
    (net (code "63") (name "Net-(7SEG2-B)") (class "Default")
      (node (ref "7SEG2") (pin "6") (pinfunction "B_6") (pintype "bidirectional"))
      (node (ref "R38") (pin "2") (pinfunction "2_2") (pintype "bidirectional"))
    )
    (net (code "64") (name "Net-(7SEG2-C)") (class "Default")
      (node (ref "7SEG2") (pin "4") (pinfunction "C_4") (pintype "bidirectional"))
      (node (ref "R30") (pin "2") (pinfunction "2_2") (pintype "bidirectional"))
    )
    (net (code "65") (name "Net-(7SEG2-D)") (class "Default")
      (node (ref "7SEG2") (pin "2") (pinfunction "D_2") (pintype "bidirectional"))
      (node (ref "R32") (pin "2") (pinfunction "2_2") (pintype "bidirectional"))
    )
    (net (code "66") (name "Net-(7SEG2-D.P)") (class "Default")
      (node (ref "7SEG2") (pin "5") (pinfunction "D.P_5") (pintype "bidirectional"))
      (node (ref "R28") (pin "2") (pinfunction "2_2") (pintype "bidirectional"))
    )
    (net (code "67") (name "Net-(7SEG2-E)") (class "Default")
      (node (ref "7SEG2") (pin "1") (pinfunction "E_1") (pintype "bidirectional"))
      (node (ref "R34") (pin "2") (pinfunction "2_2") (pintype "bidirectional"))
    )
    (net (code "68") (name "Net-(7SEG2-F)") (class "Default")
      (node (ref "7SEG2") (pin "9") (pinfunction "F_9") (pintype "bidirectional"))
      (node (ref "R42") (pin "2") (pinfunction "2_2") (pintype "bidirectional"))
    )
    (net (code "69") (name "Net-(7SEG2-G)") (class "Default")
      (node (ref "7SEG2") (pin "10") (pinfunction "G_10") (pintype "bidirectional"))
      (node (ref "R45") (pin "2") (pinfunction "2_2") (pintype "bidirectional"))
    )
    (net (code "70") (name "Net-(FB1-P$1)") (class "Default")
      (node (ref "C27") (pin "1") (pinfunction "1_1") (pintype "bidirectional"))
      (node (ref "FB1") (pin "1") (pinfunction "P$1_1") (pintype "bidirectional"))
      (node (ref "USB") (pin "1") (pinfunction "1_1") (pintype "bidirectional"))
    )
    (net (code "71") (name "Net-(FB1-P$2)") (class "Default")
      (node (ref "FB1") (pin "2") (pinfunction "P$2_2") (pintype "bidirectional"))
      (node (ref "IC6") (pin "3") (pinfunction "VCC_3") (pintype "power_in"))
      (node (ref "IC6") (pin "42") (pinfunction "VCC_42") (pintype "power_in"))
      (node (ref "R13") (pin "1") (pinfunction "1_1") (pintype "bidirectional"))
    )
    (net (code "72") (name "Net-(IC1-CCLK)") (class "Default")
      (node (ref "IC1") (pin "50") (pinfunction "CCLK_50") (pintype "bidirectional"))
      (node (ref "IC2") (pin "3") (pinfunction "CLK_3") (pintype "bidirectional"))
    )
    (net (code "73") (name "Net-(IC1-DIN)") (class "Default")
      (node (ref "IC1") (pin "44") (pinfunction "DIN_44") (pintype "bidirectional"))
      (node (ref "IC2") (pin "1") (pinfunction "D0_1") (pintype "bidirectional"))
    )
    (net (code "74") (name "Net-(IC1-DONE)") (class "Default")
      (node (ref "DONE") (pin "A") (pinfunction "A_A") (pintype "passive"))
      (node (ref "IC1") (pin "51") (pinfunction "DONE_51") (pintype "bidirectional"))
      (node (ref "R1") (pin "2") (pinfunction "2_2") (pintype "bidirectional"))
    )
    (net (code "75") (name "Net-(IC1-HSWAP)") (class "Default")
      (node (ref "IC1") (pin "99") (pinfunction "HSWAP_99") (pintype "bidirectional"))
      (node (ref "R4") (pin "2") (pinfunction "2_2") (pintype "bidirectional"))
    )
    (net (code "76") (name "Net-(IC1-INIT_B)") (class "Default")
      (node (ref "IC1") (pin "25") (pinfunction "INIT_B_25") (pintype "bidirectional"))
      (node (ref "IC2") (pin "8") (pinfunction "OE/NRST_8") (pintype "bidirectional"))
      (node (ref "R3") (pin "2") (pinfunction "2_2") (pintype "bidirectional"))
    )
    (net (code "77") (name "Net-(IC1-PROG_B)") (class "Default")
      (node (ref "IC1") (pin "1") (pinfunction "PROG_B_1") (pintype "bidirectional"))
      (node (ref "IC2") (pin "7") (pinfunction "CF__7") (pintype "bidirectional"))
      (node (ref "R2") (pin "2") (pinfunction "2_2") (pintype "bidirectional"))
    )
    (net (code "78") (name "Net-(IC3-1G_)") (class "Default")
      (node (ref "IC3") (pin "1") (pinfunction "1G__1") (pintype "bidirectional"))
      (node (ref "IC3") (pin "10") (pinfunction "3G__10") (pintype "bidirectional"))
      (node (ref "IC3") (pin "13") (pinfunction "4G__13") (pintype "bidirectional"))
      (node (ref "IC3") (pin "4") (pinfunction "2G__4") (pintype "bidirectional"))
      (node (ref "JP1") (pin "P$2") (pinfunction "P$2_P$2") (pintype "bidirectional"))
      (node (ref "R6") (pin "1") (pinfunction "1_1") (pintype "bidirectional"))
    )
    (net (code "79") (name "Net-(IC3-2A)") (class "Default")
      (node (ref "IC3") (pin "5") (pinfunction "2A_5") (pintype "bidirectional"))
      (node (ref "R5") (pin "2") (pinfunction "2_2") (pintype "bidirectional"))
    )
    (net (code "80") (name "Net-(IC3-3A)") (class "Default")
      (node (ref "IC3") (pin "9") (pinfunction "3A_9") (pintype "bidirectional"))
      (node (ref "R7") (pin "2") (pinfunction "2_2") (pintype "bidirectional"))
    )
    (net (code "81") (name "Net-(IC3-4A)") (class "Default")
      (node (ref "IC3") (pin "12") (pinfunction "4A_12") (pintype "bidirectional"))
      (node (ref "R8") (pin "2") (pinfunction "2_2") (pintype "bidirectional"))
    )
    (net (code "82") (name "Net-(IC4-DLY)") (class "Default")
      (node (ref "C21") (pin "1") (pinfunction "1_1") (pintype "bidirectional"))
      (node (ref "IC4") (pin "5") (pinfunction "DLY_5") (pintype "bidirectional"))
      (node (ref "RESET") (pin "1") (pinfunction "1_1") (pintype "bidirectional"))
      (node (ref "RESET") (pin "2") (pinfunction "2_2") (pintype "bidirectional"))
    )
    (net (code "83") (name "Net-(IC4-IN)") (class "Default")
      (node (ref "IC4") (pin "2") (pinfunction "IN_2") (pintype "bidirectional"))
      (node (ref "R12") (pin "1") (pinfunction "1_1") (pintype "bidirectional"))
      (node (ref "R9") (pin "2") (pinfunction "2_2") (pintype "bidirectional"))
    )
    (net (code "84") (name "Net-(IC5-IN1)") (class "Default")
      (node (ref "C23") (pin "1") (pinfunction "1_1") (pintype "bidirectional"))
      (node (ref "IC5") (pin "1") (pinfunction "IN1_1") (pintype "bidirectional"))
      (node (ref "R22") (pin "2") (pinfunction "2_2") (pintype "bidirectional"))
    )
    (net (code "85") (name "Net-(IC5-IN2)") (class "Default")
      (node (ref "C24") (pin "1") (pinfunction "1_1") (pintype "bidirectional"))
      (node (ref "IC5") (pin "3") (pinfunction "IN2_3") (pintype "bidirectional"))
      (node (ref "R23") (pin "2") (pinfunction "2_2") (pintype "bidirectional"))
    )
    (net (code "86") (name "Net-(IC5-IN3)") (class "Default")
      (node (ref "C25") (pin "1") (pinfunction "1_1") (pintype "bidirectional"))
      (node (ref "IC5") (pin "5") (pinfunction "IN3_5") (pintype "bidirectional"))
      (node (ref "R24") (pin "2") (pinfunction "2_2") (pintype "bidirectional"))
    )
    (net (code "87") (name "Net-(IC5-IN4)") (class "Default")
      (node (ref "C26") (pin "1") (pinfunction "1_1") (pintype "bidirectional"))
      (node (ref "IC5") (pin "9") (pinfunction "IN4_9") (pintype "bidirectional"))
      (node (ref "R25") (pin "2") (pinfunction "2_2") (pintype "bidirectional"))
    )
    (net (code "88") (name "Net-(IC5-IN5)") (class "Default")
      (node (ref "IC5") (pin "11") (pinfunction "IN5_11") (pintype "bidirectional"))
      (node (ref "R20") (pin "1") (pinfunction "1_1") (pintype "bidirectional"))
    )
    (net (code "89") (name "Net-(IC5-IN6)") (class "Default")
      (node (ref "IC5") (pin "13") (pinfunction "IN6_13") (pintype "bidirectional"))
      (node (ref "R21") (pin "1") (pinfunction "1_1") (pintype "bidirectional"))
    )
    (net (code "90") (name "Net-(IC6-3V3OUT)") (class "Default")
      (node (ref "C28") (pin "1") (pinfunction "1_1") (pintype "bidirectional"))
      (node (ref "IC6") (pin "6") (pinfunction "3V3OUT_6") (pintype "bidirectional"))
    )
    (net (code "91") (name "Net-(IC6-AVCC)") (class "Default")
      (node (ref "C22") (pin "1") (pinfunction "1_1") (pintype "bidirectional"))
      (node (ref "IC6") (pin "46") (pinfunction "AVCC_46") (pintype "power_in"))
      (node (ref "R13") (pin "2") (pinfunction "2_2") (pintype "bidirectional"))
    )
    (net (code "92") (name "Net-(IC6-BDBUS2)") (class "Default")
      (node (ref "IC6") (pin "37") (pinfunction "BDBUS3_37") (pintype "bidirectional"))
      (node (ref "IC6") (pin "38") (pinfunction "BDBUS2_38") (pintype "bidirectional"))
    )
    (net (code "93") (name "Net-(IC6-EECS)") (class "Default")
      (node (ref "IC6") (pin "48") (pinfunction "EECS_48") (pintype "bidirectional"))
      (node (ref "IC7") (pin "1") (pinfunction "CS_1") (pintype "bidirectional"))
    )
    (net (code "94") (name "Net-(IC6-EEDATA)") (class "Default")
      (node (ref "IC6") (pin "2") (pinfunction "EEDATA_2") (pintype "bidirectional"))
      (node (ref "IC7") (pin "3") (pinfunction "DI_3") (pintype "bidirectional"))
      (node (ref "R43") (pin "1") (pinfunction "1_1") (pintype "bidirectional"))
    )
    (net (code "95") (name "Net-(IC6-EESK)") (class "Default")
      (node (ref "IC6") (pin "1") (pinfunction "EESK_1") (pintype "bidirectional"))
      (node (ref "IC7") (pin "2") (pinfunction "SK_2") (pintype "bidirectional"))
    )
    (net (code "96") (name "Net-(IC6-RSTOUT_)") (class "Default")
      (node (ref "IC6") (pin "5") (pinfunction "RSTOUT__5") (pintype "bidirectional"))
      (node (ref "R26") (pin "2") (pinfunction "2_2") (pintype "bidirectional"))
    )
    (net (code "97") (name "Net-(IC6-USBDM)") (class "Default")
      (node (ref "IC6") (pin "8") (pinfunction "USBDM_8") (pintype "bidirectional"))
      (node (ref "R18") (pin "2") (pinfunction "2_2") (pintype "bidirectional"))
    )
    (net (code "98") (name "Net-(IC6-USBDP)") (class "Default")
      (node (ref "IC6") (pin "7") (pinfunction "USBDP_7") (pintype "bidirectional"))
      (node (ref "R19") (pin "2") (pinfunction "2_2") (pintype "bidirectional"))
      (node (ref "R26") (pin "1") (pinfunction "1_1") (pintype "bidirectional"))
    )
    (net (code "99") (name "Net-(IC6-XTIN)") (class "Default")
      (node (ref "C29") (pin "1") (pinfunction "1_1") (pintype "bidirectional"))
      (node (ref "IC6") (pin "43") (pinfunction "XTIN_43") (pintype "bidirectional"))
      (node (ref "U2") (pin "P$1") (pinfunction "P$1_P$1") (pintype "bidirectional"))
    )
    (net (code "100") (name "Net-(IC6-XTOUT)") (class "Default")
      (node (ref "C30") (pin "1") (pinfunction "1_1") (pintype "bidirectional"))
      (node (ref "IC6") (pin "44") (pinfunction "XTOUT_44") (pintype "bidirectional"))
      (node (ref "U2") (pin "P$2") (pinfunction "P$2_P$2") (pintype "bidirectional"))
    )
    (net (code "101") (name "Net-(IC7-DO)") (class "Default")
      (node (ref "IC7") (pin "4") (pinfunction "DO_4") (pintype "bidirectional"))
      (node (ref "R43") (pin "2") (pinfunction "2_2") (pintype "bidirectional"))
      (node (ref "R46") (pin "1") (pinfunction "1_1") (pintype "bidirectional"))
    )
    (net (code "102") (name "Net-(LED1-PadC)") (class "Default")
      (node (ref "LED1") (pin "C") (pinfunction "C_C") (pintype "passive"))
      (node (ref "R35") (pin "1") (pinfunction "1_1") (pintype "bidirectional"))
    )
    (net (code "103") (name "Net-(LED2-PadC)") (class "Default")
      (node (ref "LED2") (pin "C") (pinfunction "C_C") (pintype "passive"))
      (node (ref "R36") (pin "1") (pinfunction "1_1") (pintype "bidirectional"))
    )
    (net (code "104") (name "Net-(R11-Pad1)") (class "Default")
      (node (ref "R11") (pin "1") (pinfunction "1_1") (pintype "bidirectional"))
      (node (ref "U1") (pin "3") (pinfunction "3_3") (pintype "output"))
    )
    (net (code "105") (name "Net-(R14-Pad2)") (class "Default")
      (node (ref "R14") (pin "2") (pinfunction "2_2") (pintype "bidirectional"))
      (node (ref "R22") (pin "1") (pinfunction "1_1") (pintype "bidirectional"))
      (node (ref "SW1") (pin "1") (pinfunction "1_1") (pintype "bidirectional"))
      (node (ref "SW1") (pin "2") (pinfunction "2_2") (pintype "bidirectional"))
    )
    (net (code "106") (name "Net-(R15-Pad2)") (class "Default")
      (node (ref "R15") (pin "2") (pinfunction "2_2") (pintype "bidirectional"))
      (node (ref "R23") (pin "1") (pinfunction "1_1") (pintype "bidirectional"))
      (node (ref "SW2") (pin "1") (pinfunction "1_1") (pintype "bidirectional"))
      (node (ref "SW2") (pin "2") (pinfunction "2_2") (pintype "bidirectional"))
    )
    (net (code "107") (name "Net-(R16-Pad2)") (class "Default")
      (node (ref "R16") (pin "2") (pinfunction "2_2") (pintype "bidirectional"))
      (node (ref "R24") (pin "1") (pinfunction "1_1") (pintype "bidirectional"))
      (node (ref "SW3") (pin "1") (pinfunction "1_1") (pintype "bidirectional"))
      (node (ref "SW3") (pin "2") (pinfunction "2_2") (pintype "bidirectional"))
    )
    (net (code "108") (name "Net-(R17-Pad2)") (class "Default")
      (node (ref "R17") (pin "2") (pinfunction "2_2") (pintype "bidirectional"))
      (node (ref "R25") (pin "1") (pinfunction "1_1") (pintype "bidirectional"))
      (node (ref "SW4") (pin "1") (pinfunction "1_1") (pintype "bidirectional"))
      (node (ref "SW4") (pin "2") (pinfunction "2_2") (pintype "bidirectional"))
    )
    (net (code "109") (name "Net-(R18-Pad1)") (class "Default")
      (node (ref "R18") (pin "1") (pinfunction "1_1") (pintype "bidirectional"))
      (node (ref "USB") (pin "2") (pinfunction "2_2") (pintype "bidirectional"))
    )
    (net (code "110") (name "Net-(R19-Pad1)") (class "Default")
      (node (ref "R19") (pin "1") (pinfunction "1_1") (pintype "bidirectional"))
      (node (ref "USB") (pin "3") (pinfunction "3_3") (pintype "bidirectional"))
    )
    (net (code "111") (name "VCCAUX") (class "Default")
      (node (ref "C5") (pin "P$1") (pinfunction "1_P$1") (pintype "bidirectional"))
      (node (ref "C6") (pin "P$1") (pinfunction "1_P$1") (pintype "bidirectional"))
      (node (ref "C7") (pin "P$1") (pinfunction "1_P$1") (pintype "bidirectional"))
      (node (ref "C8") (pin "P$1") (pinfunction "1_P$1") (pintype "bidirectional"))
      (node (ref "IC1") (pin "21") (pinfunction "VCCAUX_1_21") (pintype "power_in"))
      (node (ref "IC1") (pin "46") (pinfunction "VCCAUX_2_46") (pintype "power_in"))
      (node (ref "IC1") (pin "74") (pinfunction "VCCAUX_3_74") (pintype "power_in"))
      (node (ref "IC1") (pin "96") (pinfunction "VCCAUX_4_96") (pintype "power_in"))
      (node (ref "IC2") (pin "19") (pinfunction "VCCO_19") (pintype "power_in"))
      (node (ref "IC2") (pin "20") (pinfunction "VCCJ_20") (pintype "power_in"))
      (node (ref "JP1") (pin "P$1") (pinfunction "P$1_P$1") (pintype "bidirectional"))
      (node (ref "POWER") (pin "5") (pinfunction "VCCAUX_5") (pintype "power_in"))
      (node (ref "POWER") (pin "6") (pinfunction "VCCAUX_6") (pintype "power_in"))
      (node (ref "R1") (pin "1") (pinfunction "1_1") (pintype "bidirectional"))
      (node (ref "R2") (pin "1") (pinfunction "1_1") (pintype "bidirectional"))
      (node (ref "R3") (pin "1") (pinfunction "1_1") (pintype "bidirectional"))
      (node (ref "R4") (pin "1") (pinfunction "1_1") (pintype "bidirectional"))
    )
    (net (code "112") (name "VCCINT") (class "Default")
      (node (ref "C1") (pin "P$1") (pinfunction "1_P$1") (pintype "bidirectional"))
      (node (ref "C2") (pin "P$1") (pinfunction "1_P$1") (pintype "bidirectional"))
      (node (ref "C3") (pin "P$1") (pinfunction "1_P$1") (pintype "bidirectional"))
      (node (ref "C4") (pin "P$1") (pinfunction "1_P$1") (pintype "bidirectional"))
      (node (ref "IC1") (pin "28") (pinfunction "VCCINT_2_28") (pintype "power_in"))
      (node (ref "IC1") (pin "56") (pinfunction "VCCINT_3_56") (pintype "power_in"))
      (node (ref "IC1") (pin "6") (pinfunction "VCCINT_1_6") (pintype "power_in"))
      (node (ref "IC1") (pin "80") (pinfunction "VCCINT_4_80") (pintype "power_in"))
      (node (ref "POWER") (pin "3") (pinfunction "VCCINT_3") (pintype "power_in"))
      (node (ref "POWER") (pin "4") (pinfunction "VCCINT_4") (pintype "power_in"))
    )
    (net (code "113") (name "VCCO") (class "Default")
      (node (ref "7SEG1") (pin "3") (pinfunction "COMMON3_3") (pintype "bidirectional"))
      (node (ref "7SEG1") (pin "8") (pinfunction "COMMON8_8") (pintype "bidirectional"))
      (node (ref "7SEG2") (pin "3") (pinfunction "COMMON3_3") (pintype "bidirectional"))
      (node (ref "7SEG2") (pin "8") (pinfunction "COMMON8_8") (pintype "bidirectional"))
      (node (ref "C10") (pin "P$1") (pinfunction "1_P$1") (pintype "bidirectional"))
      (node (ref "C11") (pin "P$1") (pinfunction "1_P$1") (pintype "bidirectional"))
      (node (ref "C12") (pin "P$1") (pinfunction "1_P$1") (pintype "bidirectional"))
      (node (ref "C13") (pin "P$1") (pinfunction "1_P$1") (pintype "bidirectional"))
      (node (ref "C14") (pin "P$1") (pinfunction "1_P$1") (pintype "bidirectional"))
      (node (ref "C15") (pin "P$1") (pinfunction "1_P$1") (pintype "bidirectional"))
      (node (ref "C16") (pin "P$1") (pinfunction "1_P$1") (pintype "bidirectional"))
      (node (ref "C17") (pin "P$1") (pinfunction "1_P$1") (pintype "bidirectional"))
      (node (ref "C18") (pin "1") (pinfunction "1_1") (pintype "bidirectional"))
      (node (ref "C19") (pin "1") (pinfunction "1_1") (pintype "bidirectional"))
      (node (ref "C20") (pin "1") (pinfunction "1_1") (pintype "bidirectional"))
      (node (ref "C9") (pin "P$1") (pinfunction "1_P$1") (pintype "bidirectional"))
      (node (ref "IC1") (pin "20") (pinfunction "VCCO_BK3_2_20") (pintype "power_in"))
      (node (ref "IC1") (pin "31") (pinfunction "VCCO_BK2_1_31") (pintype "power_in"))
      (node (ref "IC1") (pin "45") (pinfunction "VCCO_BK2_2_45") (pintype "power_in"))
      (node (ref "IC1") (pin "55") (pinfunction "VCCO_BK1_1_55") (pintype "power_in"))
      (node (ref "IC1") (pin "73") (pinfunction "VCCO_BK1_2_73") (pintype "power_in"))
      (node (ref "IC1") (pin "8") (pinfunction "VCCO_BK3_1_8") (pintype "power_in"))
      (node (ref "IC1") (pin "82") (pinfunction "VCCO_BK0_1_82") (pintype "power_in"))
      (node (ref "IC1") (pin "97") (pinfunction "VCCO_BK0_2_97") (pintype "power_in"))
      (node (ref "IC2") (pin "18") (pinfunction "VCCI_18") (pintype "power_in"))
      (node (ref "IC3") (pin "14") (pinfunction "VCCO_14") (pintype "power_in"))
      (node (ref "IC4") (pin "7") (pinfunction "VCCO_7") (pintype "power_in"))
      (node (ref "IC5") (pin "14") (pinfunction "VCCO_14") (pintype "power_in"))
      (node (ref "IC6") (pin "14") (pinfunction "VCCIOA_14") (pintype "power_in"))
      (node (ref "IC6") (pin "31") (pinfunction "VCCIOB_31") (pintype "power_in"))
      (node (ref "IC7") (pin "8") (pinfunction "VCC_8") (pintype "bidirectional"))
      (node (ref "LED1") (pin "A") (pinfunction "A_A") (pintype "passive"))
      (node (ref "LED2") (pin "A") (pinfunction "A_A") (pintype "passive"))
      (node (ref "POWER") (pin "7") (pinfunction "VCCO_7") (pintype "power_in"))
      (node (ref "POWER") (pin "8") (pinfunction "VCCO_8") (pintype "power_in"))
      (node (ref "R10") (pin "1") (pinfunction "1_1") (pintype "bidirectional"))
      (node (ref "R14") (pin "1") (pinfunction "1_1") (pintype "bidirectional"))
      (node (ref "R15") (pin "1") (pinfunction "1_1") (pintype "bidirectional"))
      (node (ref "R16") (pin "1") (pinfunction "1_1") (pintype "bidirectional"))
      (node (ref "R17") (pin "1") (pinfunction "1_1") (pintype "bidirectional"))
      (node (ref "R46") (pin "2") (pinfunction "2_2") (pintype "bidirectional"))
      (node (ref "R9") (pin "1") (pinfunction "1_1") (pintype "bidirectional"))
      (node (ref "U1") (pin "4") (pinfunction "4_4") (pintype "power_in"))
      (node (ref "VPD") (pin "10") (pinfunction "10_10") (pintype "power_in"))
      (node (ref "VPE") (pin "10") (pinfunction "10_10") (pintype "power_in"))
    )
    (net (code "114") (name "unconnected-(IC1-CSI_B{slash}IO_BK2-Pad27)") (class "Default")
      (node (ref "IC1") (pin "27") (pinfunction "CSI_B/IO_BK2_27") (pintype "bidirectional"))
    )
    (net (code "115") (name "unconnected-(IC1-IO_L01N_0-Pad79)") (class "Default")
      (node (ref "IC1") (pin "79") (pinfunction "IO_L01N_0_79") (pintype "bidirectional"))
    )
    (net (code "116") (name "unconnected-(IC1-IO_L01P_0-Pad78)") (class "Default")
      (node (ref "IC1") (pin "78") (pinfunction "IO_L01P_0_78") (pintype "bidirectional"))
    )
    (net (code "117") (name "unconnected-(IC1-IO_L02N_0{slash}GCLK5-Pad84)") (class "Default")
      (node (ref "IC1") (pin "84") (pinfunction "IO_L02N_0/GCLK5_84") (pintype "bidirectional"))
    )
    (net (code "118") (name "unconnected-(IC1-IO_L03P_2{slash}D7{slash}GCLK12-Pad32)") (class "Default")
      (node (ref "IC1") (pin "32") (pinfunction "IO_L03P_2/D7/GCLK12_32") (pintype "bidirectional"))
    )
    (net (code "119") (name "unconnected-(IC1-IO_L06N_3{slash}LHCLK7-Pad18)") (class "Default")
      (node (ref "IC1") (pin "18") (pinfunction "IO_L06N_3/LHCLK7_18") (pintype "bidirectional"))
    )
    (net (code "120") (name "unconnected-(IC1-IO_L06P_3{slash}LHCLK6-Pad17)") (class "Default")
      (node (ref "IC1") (pin "17") (pinfunction "IO_L06P_3/LHCLK6_17") (pintype "bidirectional"))
    )
    (net (code "121") (name "unconnected-(IC1-IO_L07P_0-Pad98)") (class "Default")
      (node (ref "IC1") (pin "98") (pinfunction "IO_L07P_0_98") (pintype "bidirectional"))
    )
    (net (code "122") (name "unconnected-(IC1-IO_L08N_2{slash}VS1-Pad48)") (class "Default")
      (node (ref "IC1") (pin "48") (pinfunction "IO_L08N_2/VS1_48") (pintype "bidirectional"))
    )
    (net (code "123") (name "unconnected-(IC1-IO_L08P_2{slash}VS2-Pad47)") (class "Default")
      (node (ref "IC1") (pin "47") (pinfunction "IO_L08P_2/VS2_47") (pintype "bidirectional"))
    )
    (net (code "124") (name "unconnected-(IC1-IO_L09P_2{slash}VS0-Pad49)") (class "Default")
      (node (ref "IC1") (pin "49") (pinfunction "IO_L09P_2/VS0_49") (pintype "bidirectional"))
    )
    (net (code "125") (name "unconnected-(IC1-IP_BK2{slash}GCLK0{slash}NWR-Pad38)") (class "Default")
      (node (ref "IC1") (pin "38") (pinfunction "IP_BK2/GCLK0/NWR_38") (pintype "input"))
    )
    (net (code "126") (name "unconnected-(IC1-IP_BK3-Pad13)") (class "Default")
      (node (ref "IC1") (pin "13") (pinfunction "IP_BK3_13") (pintype "input"))
    )
    (net (code "127") (name "unconnected-(IC1-IP_L04N_0{slash}GCLK9-Pad89)") (class "Default")
      (node (ref "IC1") (pin "89") (pinfunction "IP_L04N_0/GCLK9_89") (pintype "input"))
    )
    (net (code "128") (name "unconnected-(IC1-IP_L04P_0{slash}GCLK8-Pad88)") (class "Default")
      (node (ref "IC1") (pin "88") (pinfunction "IP_L04P_0/GCLK8_88") (pintype "input"))
    )
    (net (code "129") (name "unconnected-(IC1-IP{slash}VREF_1-Pad69)") (class "Default")
      (node (ref "IC1") (pin "69") (pinfunction "IP/VREF_1_69") (pintype "input"))
    )
    (net (code "130") (name "unconnected-(IC1-IP{slash}VREF_2-Pad30)") (class "Default")
      (node (ref "IC1") (pin "30") (pinfunction "IP/VREF_2_30") (pintype "input"))
    )
    (net (code "131") (name "unconnected-(IC2-CEO_-Pad13)") (class "Default")
      (node (ref "IC2") (pin "13") (pinfunction "CEO__13") (pintype "bidirectional"))
    )
    (net (code "132") (name "unconnected-(IC2-NC1-Pad2)") (class "Default")
      (node (ref "IC2") (pin "2") (pinfunction "NC1_2") (pintype "no_connect"))
    )
    (net (code "133") (name "unconnected-(IC2-NC2-Pad9)") (class "Default")
      (node (ref "IC2") (pin "9") (pinfunction "NC2_9") (pintype "no_connect"))
    )
    (net (code "134") (name "unconnected-(IC2-NC3-Pad12)") (class "Default")
      (node (ref "IC2") (pin "12") (pinfunction "NC3_12") (pintype "no_connect"))
    )
    (net (code "135") (name "unconnected-(IC2-NC4-Pad14)") (class "Default")
      (node (ref "IC2") (pin "14") (pinfunction "NC4_14") (pintype "no_connect"))
    )
    (net (code "136") (name "unconnected-(IC2-NC5-Pad15)") (class "Default")
      (node (ref "IC2") (pin "15") (pinfunction "NC5_15") (pintype "no_connect"))
    )
    (net (code "137") (name "unconnected-(IC2-NC6-Pad16)") (class "Default")
      (node (ref "IC2") (pin "16") (pinfunction "NC6_16") (pintype "no_connect"))
    )
    (net (code "138") (name "unconnected-(IC4-NC-Pad1)") (class "Default")
      (node (ref "IC4") (pin "1") (pinfunction "NC_1") (pintype "bidirectional"))
    )
    (net (code "139") (name "unconnected-(IC4-NC-Pad3)") (class "Default")
      (node (ref "IC4") (pin "3") (pinfunction "NC_3") (pintype "bidirectional"))
    )
    (net (code "140") (name "unconnected-(IC4-NC-Pad8)") (class "Default")
      (node (ref "IC4") (pin "8") (pinfunction "NC_8") (pintype "bidirectional"))
    )
    (net (code "141") (name "unconnected-(IC5-OUT5-Pad10)") (class "Default")
      (node (ref "IC5") (pin "10") (pinfunction "OUT5_10") (pintype "bidirectional"))
    )
    (net (code "142") (name "unconnected-(IC5-OUT6-Pad12)") (class "Default")
      (node (ref "IC5") (pin "12") (pinfunction "OUT6_12") (pintype "bidirectional"))
    )
    (net (code "143") (name "unconnected-(IC6-ACBUS0-Pad15)") (class "Default")
      (node (ref "IC6") (pin "15") (pinfunction "ACBUS0_15") (pintype "bidirectional"))
    )
    (net (code "144") (name "unconnected-(IC6-ACBUS1-Pad13)") (class "Default")
      (node (ref "IC6") (pin "13") (pinfunction "ACBUS1_13") (pintype "bidirectional"))
    )
    (net (code "145") (name "unconnected-(IC6-ACBUS2-Pad12)") (class "Default")
      (node (ref "IC6") (pin "12") (pinfunction "ACBUS2_12") (pintype "bidirectional"))
    )
    (net (code "146") (name "unconnected-(IC6-ACBUS3-Pad11)") (class "Default")
      (node (ref "IC6") (pin "11") (pinfunction "ACBUS3_11") (pintype "bidirectional"))
    )
    (net (code "147") (name "unconnected-(IC6-ADBUS5-Pad19)") (class "Default")
      (node (ref "IC6") (pin "19") (pinfunction "ADBUS5_19") (pintype "bidirectional"))
    )
    (net (code "148") (name "unconnected-(IC6-ADBUS6-Pad17)") (class "Default")
      (node (ref "IC6") (pin "17") (pinfunction "ADBUS6_17") (pintype "bidirectional"))
    )
    (net (code "149") (name "unconnected-(IC6-ADBUS7-Pad16)") (class "Default")
      (node (ref "IC6") (pin "16") (pinfunction "ADBUS7_16") (pintype "bidirectional"))
    )
    (net (code "150") (name "unconnected-(IC6-BCBUS0-Pad30)") (class "Default")
      (node (ref "IC6") (pin "30") (pinfunction "BCBUS0_30") (pintype "bidirectional"))
    )
    (net (code "151") (name "unconnected-(IC6-BCBUS1-Pad29)") (class "Default")
      (node (ref "IC6") (pin "29") (pinfunction "BCBUS1_29") (pintype "bidirectional"))
    )
    (net (code "152") (name "unconnected-(IC6-BCBUS2-Pad28)") (class "Default")
      (node (ref "IC6") (pin "28") (pinfunction "BCBUS2_28") (pintype "bidirectional"))
    )
    (net (code "153") (name "unconnected-(IC6-BCBUS3-Pad27)") (class "Default")
      (node (ref "IC6") (pin "27") (pinfunction "BCBUS3_27") (pintype "bidirectional"))
    )
    (net (code "154") (name "unconnected-(IC6-BDBUS4-Pad36)") (class "Default")
      (node (ref "IC6") (pin "36") (pinfunction "BDBUS4_36") (pintype "bidirectional"))
    )
    (net (code "155") (name "unconnected-(IC6-BDBUS5-Pad35)") (class "Default")
      (node (ref "IC6") (pin "35") (pinfunction "BDBUS5_35") (pintype "bidirectional"))
    )
    (net (code "156") (name "unconnected-(IC6-BDBUS6-Pad33)") (class "Default")
      (node (ref "IC6") (pin "33") (pinfunction "BDBUS6_33") (pintype "bidirectional"))
    )
    (net (code "157") (name "unconnected-(IC6-BDBUS7-Pad32)") (class "Default")
      (node (ref "IC6") (pin "32") (pinfunction "BDBUS7_32") (pintype "bidirectional"))
    )
    (net (code "158") (name "unconnected-(IC6-PWREN_-Pad41)") (class "Default")
      (node (ref "IC6") (pin "41") (pinfunction "PWREN__41") (pintype "bidirectional"))
    )
    (net (code "159") (name "unconnected-(IC6-RESET_-Pad4)") (class "Default")
      (node (ref "IC6") (pin "4") (pinfunction "RESET__4") (pintype "bidirectional"))
    )
    (net (code "160") (name "unconnected-(IC6-SI{slash}WUA-Pad10)") (class "Default")
      (node (ref "IC6") (pin "10") (pinfunction "SI/WUA_10") (pintype "bidirectional"))
    )
    (net (code "161") (name "unconnected-(IC6-SI{slash}WUB-Pad26)") (class "Default")
      (node (ref "IC6") (pin "26") (pinfunction "SI/WUB_26") (pintype "bidirectional"))
    )
    (net (code "162") (name "unconnected-(IC7-NC-Pad7)") (class "Default")
      (node (ref "IC7") (pin "7") (pinfunction "NC_7") (pintype "bidirectional"))
    )
    (net (code "163") (name "unconnected-(IC7-ORG-Pad6)") (class "Default")
      (node (ref "IC7") (pin "6") (pinfunction "ORG_6") (pintype "bidirectional"))
    )
    (net (code "164") (name "unconnected-(U1-Pad1)") (class "Default")
      (node (ref "U1") (pin "1") (pinfunction "1_1") (pintype "bidirectional"))
    )
  )
)
